# m328p_rfm69_node.net
KiCad netlist of a schematic drawn in EAGLE
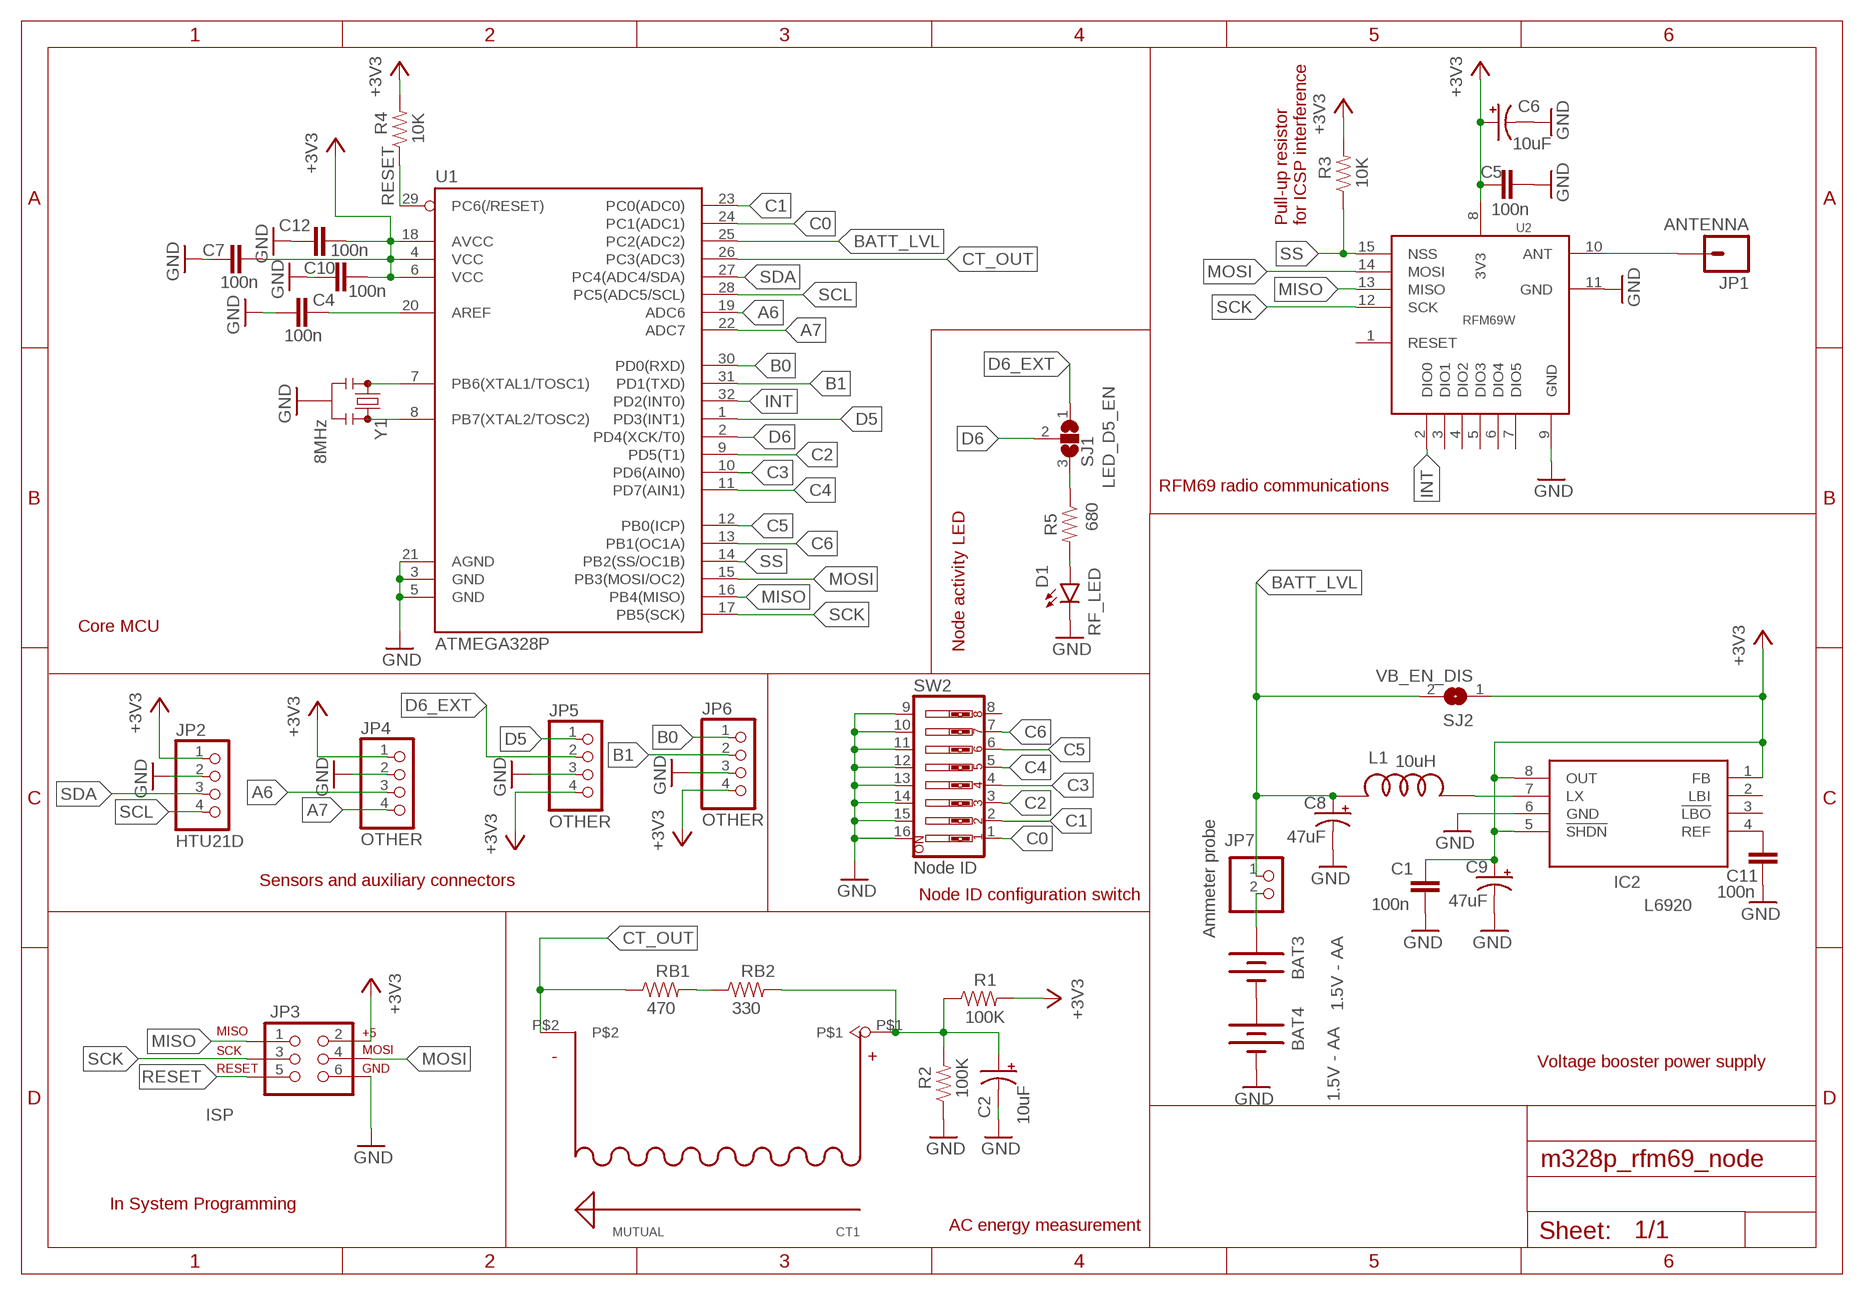
[diagram p0: schematic, sheet 1]

(export (version "E")
  (design (tool "Eeschema 10.0.6"))
  (components
    (comp (ref "BAT3")
      (value "1.5V - AA")
      (footprint "eagle-import:BATTERY-AAA-KIT")
      (libsource (lib "eagle-import") (part "BATTERYAAA-KIT"))
    )
    (comp (ref "BAT4")
      (value "1.5V - AA")
      (footprint "eagle-import:BATTERY-AAA-KIT")
      (libsource (lib "eagle-import") (part "BATTERYAAA-KIT"))
    )
    (comp (ref "C1")
      (value "100n")
      (footprint "eagle-import:0805")
      (libsource (lib "eagle-import") (part "CAP0805"))
    )
    (comp (ref "C2")
      (value "10uF")
      (footprint "eagle-import:EIA3528")
      (libsource (lib "eagle-import") (part "47UF-TANT"))
    )
    (comp (ref "C4")
      (value "100n")
      (footprint "eagle-import:0805")
      (libsource (lib "eagle-import") (part "CAP0805"))
    )
    (comp (ref "C5")
      (value "100n")
      (footprint "eagle-import:0805")
      (libsource (lib "eagle-import") (part "CAP0805"))
    )
    (comp (ref "C6")
      (value "10uF")
      (footprint "eagle-import:EIA3528")
      (libsource (lib "eagle-import") (part "47UF-TANT"))
    )
    (comp (ref "C7")
      (value "100n")
      (footprint "eagle-import:0805")
      (libsource (lib "eagle-import") (part "CAP0805"))
    )
    (comp (ref "C8")
      (value "47uF")
      (footprint "eagle-import:EIA3528")
      (libsource (lib "eagle-import") (part "47UF-TANT"))
    )
    (comp (ref "C9")
      (value "47uF")
      (footprint "eagle-import:EIA3528")
      (libsource (lib "eagle-import") (part "47UF-TANT"))
    )
    (comp (ref "C10")
      (value "100n")
      (footprint "eagle-import:0805")
      (libsource (lib "eagle-import") (part "CAP0805"))
    )
    (comp (ref "C11")
      (value "100n")
      (footprint "eagle-import:0805")
      (libsource (lib "eagle-import") (part "CAP0805"))
    )
    (comp (ref "C12")
      (value "100n")
      (footprint "eagle-import:0805")
      (libsource (lib "eagle-import") (part "CAP0805"))
    )
    (comp (ref "CT1")
      (value "MUTUAL")
      (footprint "eagle-import:MUTUAL")
      (libsource (lib "eagle-import") (part "MUTUAL"))
    )
    (comp (ref "D1")
      (value "RF_LED")
      (footprint "eagle-import:LED-0603")
      (libsource (lib "eagle-import") (part "LED0603"))
    )
    (comp (ref "IC2")
      (value "L6920")
      (footprint "eagle-import:TSSOP8")
      (libsource (lib "eagle-import") (part "L6920TSSOP8"))
    )
    (comp (ref "JP1")
      (value "ANTENNA")
      (footprint "eagle-import:LUXEON-PAD")
      (libsource (lib "eagle-import") (part "M01SMD"))
    )
    (comp (ref "JP2")
      (value "HTU21D")
      (footprint "eagle-import:1X04")
      (libsource (lib "eagle-import") (part "PINHD-1X4"))
    )
    (comp (ref "JP3")
      (value "ISP")
      (footprint "eagle-import:2X3")
      (libsource (lib "eagle-import") (part "AVR_SPI_PRG_6PTH"))
    )
    (comp (ref "JP4")
      (value "OTHER")
      (footprint "eagle-import:1X04")
      (libsource (lib "eagle-import") (part "PINHD-1X4"))
    )
    (comp (ref "JP5")
      (value "OTHER")
      (footprint "eagle-import:1X04")
      (libsource (lib "eagle-import") (part "PINHD-1X4"))
    )
    (comp (ref "JP6")
      (value "OTHER")
      (footprint "eagle-import:1X04")
      (libsource (lib "eagle-import") (part "PINHD-1X4"))
    )
    (comp (ref "JP7")
      (value "Ammeter probe")
      (footprint "eagle-import:1X02")
      (libsource (lib "eagle-import") (part "PINHD-1X2"))
    )
    (comp (ref "L1")
      (value "10uH")
      (footprint "eagle-import:DLJ-4018")
      (libsource (lib "eagle-import") (part "DLJ-4018"))
    )
    (comp (ref "R1")
      (value "100K")
      (footprint "eagle-import:0805")
      (libsource (lib "eagle-import") (part "SparkFun-Resistors_RESISTOR0805-RES"))
    )
    (comp (ref "R2")
      (value "100K")
      (footprint "eagle-import:0805")
      (libsource (lib "eagle-import") (part "SparkFun-Resistors_RESISTOR0805-RES"))
    )
    (comp (ref "R3")
      (value "10K")
      (footprint "eagle-import:0805")
      (libsource (lib "eagle-import") (part "SparkFun-Resistors_RESISTOR0805-RES"))
    )
    (comp (ref "R4")
      (value "10K")
      (footprint "eagle-import:0805")
      (libsource (lib "eagle-import") (part "SparkFun-Resistors_RESISTOR0805-RES"))
    )
    (comp (ref "R5")
      (value "680")
      (footprint "eagle-import:0805")
      (libsource (lib "eagle-import") (part "RESISTOR0805-RES"))
    )
    (comp (ref "RB1")
      (value "470")
      (footprint "eagle-import:0805")
      (libsource (lib "eagle-import") (part "SparkFun-Resistors_RESISTOR0805-RES"))
    )
    (comp (ref "RB2")
      (value "330")
      (footprint "eagle-import:0805")
      (libsource (lib "eagle-import") (part "SparkFun-Resistors_RESISTOR0805-RES"))
    )
    (comp (ref "SJ1")
      (value "LED_D5_EN")
      (footprint "eagle-import:SJ_2")
      (libsource (lib "eagle-import") (part "SJ2W"))
    )
    (comp (ref "SJ2")
      (value "VB_EN_DIS")
      (footprint "eagle-import:SJ")
      (libsource (lib "eagle-import") (part "SJ"))
    )
    (comp (ref "SW2")
      (value "Node ID")
      (footprint "eagle-import:DIPSWITCH-08-50MIL")
      (libsource (lib "eagle-import") (part "SW_DIP-8-SMT-HALFSIZE"))
    )
    (comp (ref "U1")
      (value "ATMEGA328P")
      (footprint "eagle-import:TQFP32-08")
      (libsource (lib "eagle-import") (part "ATMEGA328P_TQFP"))
    )
    (comp (ref "U2")
      (value "RFM69W")
      (footprint "eagle-import:RFM69W")
      (libsource (lib "eagle-import") (part "RFM69W"))
    )
    (comp (ref "Y1")
      (value "8MHz")
      (footprint "eagle-import:RESONATOR-SMD_MED")
      (libsource (lib "eagle-import") (part "RESONATOR4MHZ"))
    )
  )
  (nets
    (net (code "1") (name "+3V3") (class "Default")
      (node (ref "C1") (pin "1") (pinfunction "1_1") (pintype "passive"))
      (node (ref "C10") (pin "2") (pinfunction "2_2") (pintype "passive"))
      (node (ref "C12") (pin "2") (pinfunction "2_2") (pintype "passive"))
      (node (ref "C5") (pin "1") (pinfunction "1_1") (pintype "passive"))
      (node (ref "C6") (pin "A") (pinfunction "+_A") (pintype "passive"))
      (node (ref "C7") (pin "2") (pinfunction "2_2") (pintype "passive"))
      (node (ref "C9") (pin "A") (pinfunction "+_A") (pintype "passive"))
      (node (ref "IC2") (pin "1") (pinfunction "FB_1") (pintype "bidirectional"))
      (node (ref "IC2") (pin "5") (pinfunction "~{SHDN}_5") (pintype "bidirectional"))
      (node (ref "IC2") (pin "8") (pinfunction "OUT_8") (pintype "bidirectional"))
      (node (ref "JP2") (pin "1") (pinfunction "1_1") (pintype "passive"))
      (node (ref "JP3") (pin "2") (pinfunction "2_2") (pintype "passive"))
      (node (ref "JP4") (pin "1") (pinfunction "1_1") (pintype "passive"))
      (node (ref "JP5") (pin "4") (pinfunction "4_4") (pintype "passive"))
      (node (ref "JP6") (pin "4") (pinfunction "4_4") (pintype "passive"))
      (node (ref "R1") (pin "2") (pinfunction "2_2") (pintype "passive"))
      (node (ref "R3") (pin "2") (pinfunction "2_2") (pintype "passive"))
      (node (ref "R4") (pin "2") (pinfunction "2_2") (pintype "passive"))
      (node (ref "SJ2") (pin "1") (pinfunction "1_1") (pintype "passive"))
      (node (ref "U1") (pin "18") (pinfunction "AVCC_18") (pintype "bidirectional"))
      (node (ref "U1") (pin "4") (pinfunction "VCC_4") (pintype "bidirectional"))
      (node (ref "U1") (pin "6") (pinfunction "VCC_6") (pintype "bidirectional"))
      (node (ref "U2") (pin "8") (pinfunction "3V3_8") (pintype "bidirectional"))
    )
    (net (code "2") (name "A6") (class "Default")
      (node (ref "JP4") (pin "3") (pinfunction "3_3") (pintype "passive"))
      (node (ref "U1") (pin "19") (pinfunction "ADC6_19") (pintype "bidirectional"))
    )
    (net (code "3") (name "A7") (class "Default")
      (node (ref "JP4") (pin "4") (pinfunction "4_4") (pintype "passive"))
      (node (ref "U1") (pin "22") (pinfunction "ADC7_22") (pintype "bidirectional"))
    )
    (net (code "4") (name "B0") (class "Default")
      (node (ref "JP6") (pin "1") (pinfunction "1_1") (pintype "passive"))
      (node (ref "U1") (pin "30") (pinfunction "PD0(RXD)_30") (pintype "bidirectional"))
    )
    (net (code "5") (name "B1") (class "Default")
      (node (ref "JP6") (pin "2") (pinfunction "2_2") (pintype "passive"))
      (node (ref "U1") (pin "31") (pinfunction "PD1(TXD)_31") (pintype "bidirectional"))
    )
    (net (code "6") (name "BATT_LVL") (class "Default")
      (node (ref "C8") (pin "A") (pinfunction "+_A") (pintype "passive"))
      (node (ref "JP7") (pin "1") (pinfunction "1_1") (pintype "passive"))
      (node (ref "L1") (pin "P$2") (pinfunction "2_P$2") (pintype "bidirectional"))
      (node (ref "SJ2") (pin "2") (pinfunction "2_2") (pintype "passive"))
      (node (ref "U1") (pin "25") (pinfunction "PC2(ADC2)_25") (pintype "bidirectional"))
    )
    (net (code "7") (name "C0") (class "Default")
      (node (ref "SW2") (pin "1") (pinfunction "1_1") (pintype "passive"))
      (node (ref "U1") (pin "24") (pinfunction "PC1(ADC1)_24") (pintype "bidirectional"))
    )
    (net (code "8") (name "C1") (class "Default")
      (node (ref "SW2") (pin "2") (pinfunction "2_2") (pintype "passive"))
      (node (ref "U1") (pin "23") (pinfunction "PC0(ADC0)_23") (pintype "bidirectional"))
    )
    (net (code "9") (name "C2") (class "Default")
      (node (ref "SW2") (pin "3") (pinfunction "3_3") (pintype "passive"))
      (node (ref "U1") (pin "9") (pinfunction "PD5(T1)_9") (pintype "bidirectional"))
    )
    (net (code "10") (name "C3") (class "Default")
      (node (ref "SW2") (pin "4") (pinfunction "4_4") (pintype "passive"))
      (node (ref "U1") (pin "10") (pinfunction "PD6(AIN0)_10") (pintype "bidirectional"))
    )
    (net (code "11") (name "C4") (class "Default")
      (node (ref "SW2") (pin "5") (pinfunction "5_5") (pintype "passive"))
      (node (ref "U1") (pin "11") (pinfunction "PD7(AIN1)_11") (pintype "bidirectional"))
    )
    (net (code "12") (name "C5") (class "Default")
      (node (ref "SW2") (pin "6") (pinfunction "6_6") (pintype "passive"))
      (node (ref "U1") (pin "12") (pinfunction "PB0(ICP)_12") (pintype "bidirectional"))
    )
    (net (code "13") (name "C6") (class "Default")
      (node (ref "SW2") (pin "7") (pinfunction "7_7") (pintype "passive"))
      (node (ref "U1") (pin "13") (pinfunction "PB1(OC1A)_13") (pintype "bidirectional"))
    )
    (net (code "14") (name "CT_OUT") (class "Default")
      (node (ref "CT1") (pin "P$2") (pinfunction "P$2_P$2") (pintype "bidirectional"))
      (node (ref "RB1") (pin "1") (pinfunction "1_1") (pintype "passive"))
      (node (ref "U1") (pin "26") (pinfunction "PC3(ADC3)_26") (pintype "bidirectional"))
    )
    (net (code "15") (name "D5") (class "Default")
      (node (ref "JP5") (pin "1") (pinfunction "1_1") (pintype "passive"))
      (node (ref "U1") (pin "1") (pinfunction "PD3(INT1)_1") (pintype "bidirectional"))
    )
    (net (code "16") (name "D6") (class "Default")
      (node (ref "SJ1") (pin "2") (pinfunction "2_2") (pintype "passive"))
      (node (ref "U1") (pin "2") (pinfunction "PD4(XCK/T0)_2") (pintype "bidirectional"))
    )
    (net (code "17") (name "D6_EXT") (class "Default")
      (node (ref "JP5") (pin "2") (pinfunction "2_2") (pintype "passive"))
      (node (ref "SJ1") (pin "1") (pinfunction "1_1") (pintype "passive"))
    )
    (net (code "18") (name "GND") (class "Default")
      (node (ref "BAT4") (pin "GND@1") (pinfunction "-_GND@1") (pintype "power_in"))
      (node (ref "C1") (pin "2") (pinfunction "2_2") (pintype "passive"))
      (node (ref "C10") (pin "1") (pinfunction "1_1") (pintype "passive"))
      (node (ref "C11") (pin "2") (pinfunction "2_2") (pintype "passive"))
      (node (ref "C12") (pin "1") (pinfunction "1_1") (pintype "passive"))
      (node (ref "C2") (pin "C") (pinfunction "-_C") (pintype "passive"))
      (node (ref "C4") (pin "1") (pinfunction "1_1") (pintype "passive"))
      (node (ref "C5") (pin "2") (pinfunction "2_2") (pintype "passive"))
      (node (ref "C6") (pin "C") (pinfunction "-_C") (pintype "passive"))
      (node (ref "C7") (pin "1") (pinfunction "1_1") (pintype "passive"))
      (node (ref "C8") (pin "C") (pinfunction "-_C") (pintype "passive"))
      (node (ref "C9") (pin "C") (pinfunction "-_C") (pintype "passive"))
      (node (ref "D1") (pin "C") (pinfunction "C_C") (pintype "passive"))
      (node (ref "IC2") (pin "6") (pinfunction "GND_6") (pintype "bidirectional"))
      (node (ref "JP2") (pin "2") (pinfunction "2_2") (pintype "passive"))
      (node (ref "JP3") (pin "6") (pinfunction "6_6") (pintype "passive"))
      (node (ref "JP4") (pin "2") (pinfunction "2_2") (pintype "passive"))
      (node (ref "JP5") (pin "3") (pinfunction "3_3") (pintype "passive"))
      (node (ref "JP6") (pin "3") (pinfunction "3_3") (pintype "passive"))
      (node (ref "R2") (pin "1") (pinfunction "1_1") (pintype "passive"))
      (node (ref "SW2") (pin "10") (pinfunction "10_10") (pintype "passive"))
      (node (ref "SW2") (pin "11") (pinfunction "11_11") (pintype "passive"))
      (node (ref "SW2") (pin "12") (pinfunction "12_12") (pintype "passive"))
      (node (ref "SW2") (pin "13") (pinfunction "13_13") (pintype "passive"))
      (node (ref "SW2") (pin "14") (pinfunction "14_14") (pintype "passive"))
      (node (ref "SW2") (pin "15") (pinfunction "15_15") (pintype "passive"))
      (node (ref "SW2") (pin "16") (pinfunction "16_16") (pintype "passive"))
      (node (ref "SW2") (pin "9") (pinfunction "9_9") (pintype "passive"))
      (node (ref "U1") (pin "21") (pinfunction "AGND_21") (pintype "bidirectional"))
      (node (ref "U1") (pin "3") (pinfunction "GND_3") (pintype "bidirectional"))
      (node (ref "U1") (pin "5") (pinfunction "GND_5") (pintype "bidirectional"))
      (node (ref "U2") (pin "11") (pinfunction "GND_11") (pintype "bidirectional"))
      (node (ref "U2") (pin "9") (pinfunction "GND_9") (pintype "bidirectional"))
      (node (ref "Y1") (pin "2") (pinfunction "2_2") (pintype "passive"))
    )
    (net (code "19") (name "INT") (class "Default")
      (node (ref "U1") (pin "32") (pinfunction "PD2(INT0)_32") (pintype "bidirectional"))
      (node (ref "U2") (pin "2") (pinfunction "DIO0_2") (pintype "bidirectional"))
    )
    (net (code "20") (name "MISO") (class "Default")
      (node (ref "JP3") (pin "1") (pinfunction "1_1") (pintype "passive"))
      (node (ref "U1") (pin "16") (pinfunction "PB4(MISO)_16") (pintype "bidirectional"))
      (node (ref "U2") (pin "13") (pinfunction "MISO_13") (pintype "bidirectional"))
    )
    (net (code "21") (name "MOSI") (class "Default")
      (node (ref "JP3") (pin "4") (pinfunction "4_4") (pintype "passive"))
      (node (ref "U1") (pin "15") (pinfunction "PB3(MOSI/OC2)_15") (pintype "bidirectional"))
      (node (ref "U2") (pin "14") (pinfunction "MOSI_14") (pintype "bidirectional"))
    )
    (net (code "22") (name "Net-(BAT3-+)") (class "Default")
      (node (ref "BAT3") (pin "PWR@1") (pinfunction "+_PWR@1") (pintype "power_in"))
      (node (ref "JP7") (pin "2") (pinfunction "2_2") (pintype "passive"))
    )
    (net (code "23") (name "Net-(BAT3--)") (class "Default")
      (node (ref "BAT3") (pin "GND@1") (pinfunction "-_GND@1") (pintype "power_in"))
      (node (ref "BAT4") (pin "PWR@1") (pinfunction "+_PWR@1") (pintype "power_in"))
    )
    (net (code "24") (name "Net-(C2-+)") (class "Default")
      (node (ref "C2") (pin "A") (pinfunction "+_A") (pintype "passive"))
      (node (ref "CT1") (pin "P$1") (pinfunction "P$1_P$1") (pintype "bidirectional"))
      (node (ref "R1") (pin "1") (pinfunction "1_1") (pintype "passive"))
      (node (ref "R2") (pin "2") (pinfunction "2_2") (pintype "passive"))
      (node (ref "RB2") (pin "2") (pinfunction "2_2") (pintype "passive"))
    )
    (net (code "25") (name "Net-(D1-PadA)") (class "Default")
      (node (ref "D1") (pin "A") (pinfunction "A_A") (pintype "passive"))
      (node (ref "R5") (pin "2") (pinfunction "2_2") (pintype "passive"))
    )
    (net (code "26") (name "Net-(IC2-LX)") (class "Default")
      (node (ref "IC2") (pin "7") (pinfunction "LX_7") (pintype "bidirectional"))
      (node (ref "L1") (pin "P$1") (pinfunction "1_P$1") (pintype "bidirectional"))
    )
    (net (code "27") (name "Net-(IC2-REF)") (class "Default")
      (node (ref "C11") (pin "1") (pinfunction "1_1") (pintype "passive"))
      (node (ref "IC2") (pin "4") (pinfunction "REF_4") (pintype "bidirectional"))
    )
    (net (code "28") (name "Net-(JP1-1)") (class "Default")
      (node (ref "JP1") (pin "P$1") (pinfunction "1_P$1") (pintype "passive"))
      (node (ref "U2") (pin "10") (pinfunction "ANT_10") (pintype "bidirectional"))
    )
    (net (code "29") (name "Net-(R5-Pad1)") (class "Default")
      (node (ref "R5") (pin "1") (pinfunction "1_1") (pintype "passive"))
      (node (ref "SJ1") (pin "3") (pinfunction "3_3") (pintype "passive"))
    )
    (net (code "30") (name "Net-(RB1-Pad2)") (class "Default")
      (node (ref "RB1") (pin "2") (pinfunction "2_2") (pintype "passive"))
      (node (ref "RB2") (pin "1") (pinfunction "1_1") (pintype "passive"))
    )
    (net (code "31") (name "Net-(U1-AREF)") (class "Default")
      (node (ref "C4") (pin "2") (pinfunction "2_2") (pintype "passive"))
      (node (ref "U1") (pin "20") (pinfunction "AREF_20") (pintype "bidirectional"))
    )
    (net (code "32") (name "Net-(U1-PB6(XTAL1{slash}TOSC1))") (class "Default")
      (node (ref "U1") (pin "7") (pinfunction "PB6(XTAL1/TOSC1)_7") (pintype "bidirectional"))
      (node (ref "Y1") (pin "1") (pinfunction "1_1") (pintype "passive"))
    )
    (net (code "33") (name "Net-(U1-PB7(XTAL2{slash}TOSC2))") (class "Default")
      (node (ref "U1") (pin "8") (pinfunction "PB7(XTAL2/TOSC2)_8") (pintype "bidirectional"))
      (node (ref "Y1") (pin "3") (pinfunction "3_3") (pintype "passive"))
    )
    (net (code "34") (name "RESET") (class "Default")
      (node (ref "JP3") (pin "5") (pinfunction "5_5") (pintype "passive"))
      (node (ref "R4") (pin "1") (pinfunction "1_1") (pintype "passive"))
      (node (ref "U1") (pin "29") (pinfunction "PC6(/RESET)_29") (pintype "bidirectional"))
    )
    (net (code "35") (name "SCK") (class "Default")
      (node (ref "JP3") (pin "3") (pinfunction "3_3") (pintype "passive"))
      (node (ref "U1") (pin "17") (pinfunction "PB5(SCK)_17") (pintype "bidirectional"))
      (node (ref "U2") (pin "12") (pinfunction "SCK_12") (pintype "bidirectional"))
    )
    (net (code "36") (name "SCL") (class "Default")
      (node (ref "JP2") (pin "4") (pinfunction "4_4") (pintype "passive"))
      (node (ref "U1") (pin "28") (pinfunction "PC5(ADC5/SCL)_28") (pintype "bidirectional"))
    )
    (net (code "37") (name "SDA") (class "Default")
      (node (ref "JP2") (pin "3") (pinfunction "3_3") (pintype "passive"))
      (node (ref "U1") (pin "27") (pinfunction "PC4(ADC4/SDA)_27") (pintype "bidirectional"))
    )
    (net (code "38") (name "SS") (class "Default")
      (node (ref "R3") (pin "1") (pinfunction "1_1") (pintype "passive"))
      (node (ref "U1") (pin "14") (pinfunction "PB2(SS/OC1B)_14") (pintype "bidirectional"))
      (node (ref "U2") (pin "15") (pinfunction "NSS_15") (pintype "bidirectional"))
    )
    (net (code "39") (name "unconnected-(IC2-LBI-Pad2)") (class "Default")
      (node (ref "IC2") (pin "2") (pinfunction "LBI_2") (pintype "bidirectional"))
    )
    (net (code "40") (name "unconnected-(IC2-~{LBO}-Pad3)") (class "Default")
      (node (ref "IC2") (pin "3") (pinfunction "~{LBO}_3") (pintype "bidirectional"))
    )
    (net (code "41") (name "unconnected-(SW2-Pad8)") (class "Default")
      (node (ref "SW2") (pin "8") (pinfunction "8_8") (pintype "passive"))
    )
    (net (code "42") (name "unconnected-(U2-DIO1-Pad3)") (class "Default")
      (node (ref "U2") (pin "3") (pinfunction "DIO1_3") (pintype "bidirectional"))
    )
    (net (code "43") (name "unconnected-(U2-DIO2-Pad4)") (class "Default")
      (node (ref "U2") (pin "4") (pinfunction "DIO2_4") (pintype "bidirectional"))
    )
    (net (code "44") (name "unconnected-(U2-DIO3-Pad5)") (class "Default")
      (node (ref "U2") (pin "5") (pinfunction "DIO3_5") (pintype "bidirectional"))
    )
    (net (code "45") (name "unconnected-(U2-DIO4-Pad6)") (class "Default")
      (node (ref "U2") (pin "6") (pinfunction "DIO4_6") (pintype "bidirectional"))
    )
    (net (code "46") (name "unconnected-(U2-DIO5-Pad7)") (class "Default")
      (node (ref "U2") (pin "7") (pinfunction "DIO5_7") (pintype "bidirectional"))
    )
    (net (code "47") (name "unconnected-(U2-RESET-Pad1)") (class "Default")
      (node (ref "U2") (pin "1") (pinfunction "RESET_1") (pintype "bidirectional"))
    )
  )
)
